# tl494module_1.net
KiCad netlist of a schematic drawn in EAGLE
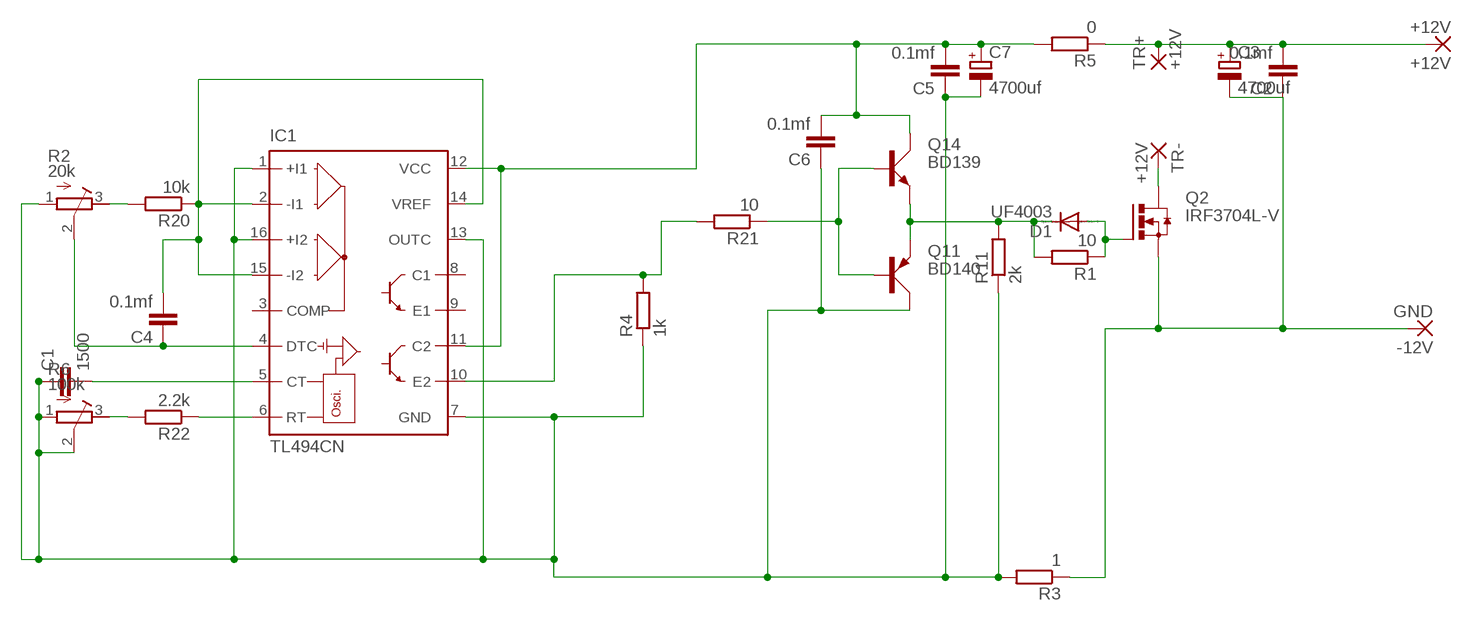
[diagram p0: schematic, sheet 1]

(export (version "E")
  (design (tool "Eeschema 10.0.6"))
  (components
    (comp (ref "+12V")
      (value "+12V")
      (footprint "eagle-import:3,81_1,1")
      (libsource (lib "eagle-import") (part "3,81/1,1"))
    )
    (comp (ref "-12V")
      (value "GND")
      (footprint "eagle-import:3,81_1,1")
      (libsource (lib "eagle-import") (part "3,81/1,1"))
    )
    (comp (ref "C1")
      (value "1500")
      (footprint "eagle-import:C050-025X075")
      (libsource (lib "eagle-import") (part "C-EU050-025X075"))
    )
    (comp (ref "C2")
      (value "0.1mf")
      (footprint "eagle-import:C050-025X075")
      (libsource (lib "eagle-import") (part "C-EU050-025X075"))
    )
    (comp (ref "C3")
      (value "4700uf")
      (footprint "eagle-import:E7,5-16")
      (libsource (lib "eagle-import") (part "CPOL-EUE7.5-16"))
    )
    (comp (ref "C4")
      (value "0.1mf")
      (footprint "eagle-import:C050-025X075")
      (libsource (lib "eagle-import") (part "C-EU050-025X075"))
    )
    (comp (ref "C5")
      (value "0.1mf")
      (footprint "eagle-import:C050-025X075")
      (libsource (lib "eagle-import") (part "C-EU050-025X075"))
    )
    (comp (ref "C6")
      (value "0.1mf")
      (footprint "eagle-import:C050-025X075")
      (libsource (lib "eagle-import") (part "C-EU050-025X075"))
    )
    (comp (ref "C7")
      (value "4700uf")
      (footprint "eagle-import:E7,5-16")
      (libsource (lib "eagle-import") (part "CPOL-EUE7.5-16"))
    )
    (comp (ref "D1")
      (value "UF4003")
      (footprint "eagle-import:DO41-10")
      (libsource (lib "eagle-import") (part "UF4003"))
    )
    (comp (ref "IC1")
      (value "TL494CN")
      (footprint "eagle-import:DIL16")
      (libsource (lib "eagle-import") (part "TL494NC"))
    )
    (comp (ref "Q2")
      (value "IRF3704L-V")
      (footprint "eagle-import:TO262-V")
      (libsource (lib "eagle-import") (part "IRF3704L-V"))
    )
    (comp (ref "Q11")
      (value "BD140")
      (footprint "eagle-import:TO126AV")
      (libsource (lib "eagle-import") (part "BD140"))
    )
    (comp (ref "Q14")
      (value "BD139")
      (footprint "eagle-import:TO126AV")
      (libsource (lib "eagle-import") (part "BD139"))
    )
    (comp (ref "R1")
      (value "10")
      (footprint "eagle-import:0204_7")
      (libsource (lib "eagle-import") (part "R-EU_0204/7"))
    )
    (comp (ref "R2")
      (value "20k")
      (footprint "eagle-import:RTRIM3296W")
      (libsource (lib "eagle-import") (part "R-TRIMM3296W"))
    )
    (comp (ref "R3")
      (value "1")
      (footprint "eagle-import:0204_7")
      (libsource (lib "eagle-import") (part "R-EU_0204/7"))
    )
    (comp (ref "R4")
      (value "1k")
      (footprint "eagle-import:0204_7")
      (libsource (lib "eagle-import") (part "R-EU_0204/7"))
    )
    (comp (ref "R5")
      (value "0")
      (footprint "eagle-import:0204_7")
      (libsource (lib "eagle-import") (part "R-EU_0204/7"))
    )
    (comp (ref "R6")
      (value "100k")
      (footprint "eagle-import:RTRIM3296W")
      (libsource (lib "eagle-import") (part "R-TRIMM3296W"))
    )
    (comp (ref "R11")
      (value "2k")
      (footprint "eagle-import:0204_7")
      (libsource (lib "eagle-import") (part "R-EU_0204/7"))
    )
    (comp (ref "R20")
      (value "10k")
      (footprint "eagle-import:0204_7")
      (libsource (lib "eagle-import") (part "R-EU_0204/7"))
    )
    (comp (ref "R21")
      (value "10")
      (footprint "eagle-import:0204_7")
      (libsource (lib "eagle-import") (part "R-EU_0204/7"))
    )
    (comp (ref "R22")
      (value "2.2k")
      (footprint "eagle-import:0204_7")
      (libsource (lib "eagle-import") (part "R-EU_0204/7"))
    )
    (comp (ref "TR+")
      (value "+12V")
      (footprint "eagle-import:3,81_1,1")
      (libsource (lib "eagle-import") (part "3,81/1,1"))
    )
    (comp (ref "TR-")
      (value "+12V")
      (footprint "eagle-import:3,81_1,1")
      (libsource (lib "eagle-import") (part "3,81/1,1"))
    )
  )
  (nets
    (net (code "1") (name "Net-(+12V-P)") (class "Default")
      (node (ref "+12V") (pin "1") (pinfunction "P_1") (pintype "passive"))
      (node (ref "C2") (pin "2") (pinfunction "2_2") (pintype "passive"))
      (node (ref "C3") (pin "+") (pinfunction "+_+") (pintype "passive"))
      (node (ref "R5") (pin "1") (pinfunction "1_1") (pintype "passive"))
      (node (ref "TR+") (pin "1") (pinfunction "P_1") (pintype "passive"))
    )
    (net (code "2") (name "Net-(-12V-P)") (class "Default")
      (node (ref "-12V") (pin "1") (pinfunction "P_1") (pintype "passive"))
      (node (ref "C2") (pin "1") (pinfunction "1_1") (pintype "passive"))
      (node (ref "C3") (pin "-") (pinfunction "-_-") (pintype "passive"))
      (node (ref "Q2") (pin "3") (pinfunction "S_3") (pintype "passive"))
      (node (ref "R3") (pin "1") (pinfunction "1_1") (pintype "passive"))
    )
    (net (code "3") (name "Net-(D1-PadC)") (class "Default")
      (node (ref "D1") (pin "C") (pinfunction "C_C") (pintype "passive"))
      (node (ref "Q11") (pin "E") (pinfunction "E_E") (pintype "passive"))
      (node (ref "Q14") (pin "E") (pinfunction "E_E") (pintype "passive"))
      (node (ref "R1") (pin "2") (pinfunction "2_2") (pintype "passive"))
      (node (ref "R11") (pin "2") (pinfunction "2_2") (pintype "passive"))
    )
    (net (code "4") (name "Net-(IC1-+I1)") (class "Default")
      (node (ref "C1") (pin "1") (pinfunction "1_1") (pintype "passive"))
      (node (ref "C5") (pin "1") (pinfunction "1_1") (pintype "passive"))
      (node (ref "C6") (pin "1") (pinfunction "1_1") (pintype "passive"))
      (node (ref "C7") (pin "-") (pinfunction "-_-") (pintype "passive"))
      (node (ref "IC1") (pin "1") (pinfunction "+I1_1") (pintype "input"))
      (node (ref "IC1") (pin "13") (pinfunction "OUTC_13") (pintype "output"))
      (node (ref "IC1") (pin "16") (pinfunction "+I2_16") (pintype "input"))
      (node (ref "IC1") (pin "7") (pinfunction "GND_7") (pintype "power_in"))
      (node (ref "Q11") (pin "C") (pinfunction "C_C") (pintype "passive"))
      (node (ref "R11") (pin "1") (pinfunction "1_1") (pintype "passive"))
      (node (ref "R2") (pin "1") (pinfunction "A_1") (pintype "passive"))
      (node (ref "R3") (pin "2") (pinfunction "2_2") (pintype "passive"))
      (node (ref "R4") (pin "1") (pinfunction "1_1") (pintype "passive"))
      (node (ref "R6") (pin "1") (pinfunction "A_1") (pintype "passive"))
      (node (ref "R6") (pin "2") (pinfunction "S_2") (pintype "passive"))
    )
    (net (code "5") (name "Net-(IC1--I1)") (class "Default")
      (node (ref "C4") (pin "2") (pinfunction "2_2") (pintype "passive"))
      (node (ref "IC1") (pin "14") (pinfunction "VREF_14") (pintype "input"))
      (node (ref "IC1") (pin "15") (pinfunction "-I2_15") (pintype "input"))
      (node (ref "IC1") (pin "2") (pinfunction "-I1_2") (pintype "input"))
      (node (ref "R20") (pin "1") (pinfunction "1_1") (pintype "passive"))
    )
    (net (code "6") (name "Net-(IC1-C2)") (class "Default")
      (node (ref "C5") (pin "2") (pinfunction "2_2") (pintype "passive"))
      (node (ref "C6") (pin "2") (pinfunction "2_2") (pintype "passive"))
      (node (ref "C7") (pin "+") (pinfunction "+_+") (pintype "passive"))
      (node (ref "IC1") (pin "11") (pinfunction "C2_11") (pintype "passive"))
      (node (ref "IC1") (pin "12") (pinfunction "VCC_12") (pintype "power_in"))
      (node (ref "Q14") (pin "C") (pinfunction "C_C") (pintype "passive"))
      (node (ref "R5") (pin "2") (pinfunction "2_2") (pintype "passive"))
    )
    (net (code "7") (name "Net-(IC1-CT)") (class "Default")
      (node (ref "C1") (pin "2") (pinfunction "2_2") (pintype "passive"))
      (node (ref "IC1") (pin "5") (pinfunction "CT_5") (pintype "input"))
    )
    (net (code "8") (name "Net-(IC1-DTC)") (class "Default")
      (node (ref "C4") (pin "1") (pinfunction "1_1") (pintype "passive"))
      (node (ref "IC1") (pin "4") (pinfunction "DTC_4") (pintype "input"))
      (node (ref "R2") (pin "2") (pinfunction "S_2") (pintype "passive"))
    )
    (net (code "9") (name "Net-(IC1-E2)") (class "Default")
      (node (ref "IC1") (pin "10") (pinfunction "E2_10") (pintype "passive"))
      (node (ref "R21") (pin "2") (pinfunction "2_2") (pintype "passive"))
      (node (ref "R4") (pin "2") (pinfunction "2_2") (pintype "passive"))
    )
    (net (code "10") (name "Net-(IC1-RT)") (class "Default")
      (node (ref "IC1") (pin "6") (pinfunction "RT_6") (pintype "input"))
      (node (ref "R22") (pin "1") (pinfunction "1_1") (pintype "passive"))
    )
    (net (code "11") (name "Net-(Q2-D)") (class "Default")
      (node (ref "Q2") (pin "2") (pinfunction "D_2") (pintype "passive"))
      (node (ref "TR-") (pin "1") (pinfunction "P_1") (pintype "passive"))
    )
    (net (code "12") (name "Net-(Q2-G)") (class "Default")
      (node (ref "D1") (pin "A") (pinfunction "A_A") (pintype "passive"))
      (node (ref "Q2") (pin "1") (pinfunction "G_1") (pintype "passive"))
      (node (ref "R1") (pin "1") (pinfunction "1_1") (pintype "passive"))
    )
    (net (code "13") (name "Net-(Q11-PadB)") (class "Default")
      (node (ref "Q11") (pin "B") (pinfunction "B_B") (pintype "passive"))
      (node (ref "Q14") (pin "B") (pinfunction "B_B") (pintype "passive"))
      (node (ref "R21") (pin "1") (pinfunction "1_1") (pintype "passive"))
    )
    (net (code "14") (name "Net-(R2-E)") (class "Default")
      (node (ref "R2") (pin "3") (pinfunction "E_3") (pintype "passive"))
      (node (ref "R20") (pin "2") (pinfunction "2_2") (pintype "passive"))
    )
    (net (code "15") (name "Net-(R6-E)") (class "Default")
      (node (ref "R22") (pin "2") (pinfunction "2_2") (pintype "passive"))
      (node (ref "R6") (pin "3") (pinfunction "E_3") (pintype "passive"))
    )
    (net (code "16") (name "unconnected-(IC1-C1-Pad8)") (class "Default")
      (node (ref "IC1") (pin "8") (pinfunction "C1_8") (pintype "passive"))
    )
    (net (code "17") (name "unconnected-(IC1-COMP-Pad3)") (class "Default")
      (node (ref "IC1") (pin "3") (pinfunction "COMP_3") (pintype "passive"))
    )
    (net (code "18") (name "unconnected-(IC1-E1-Pad9)") (class "Default")
      (node (ref "IC1") (pin "9") (pinfunction "E1_9") (pintype "passive"))
    )
  )
)
